# Processor.net
KiCad netlist of a schematic drawn in Altium Designer
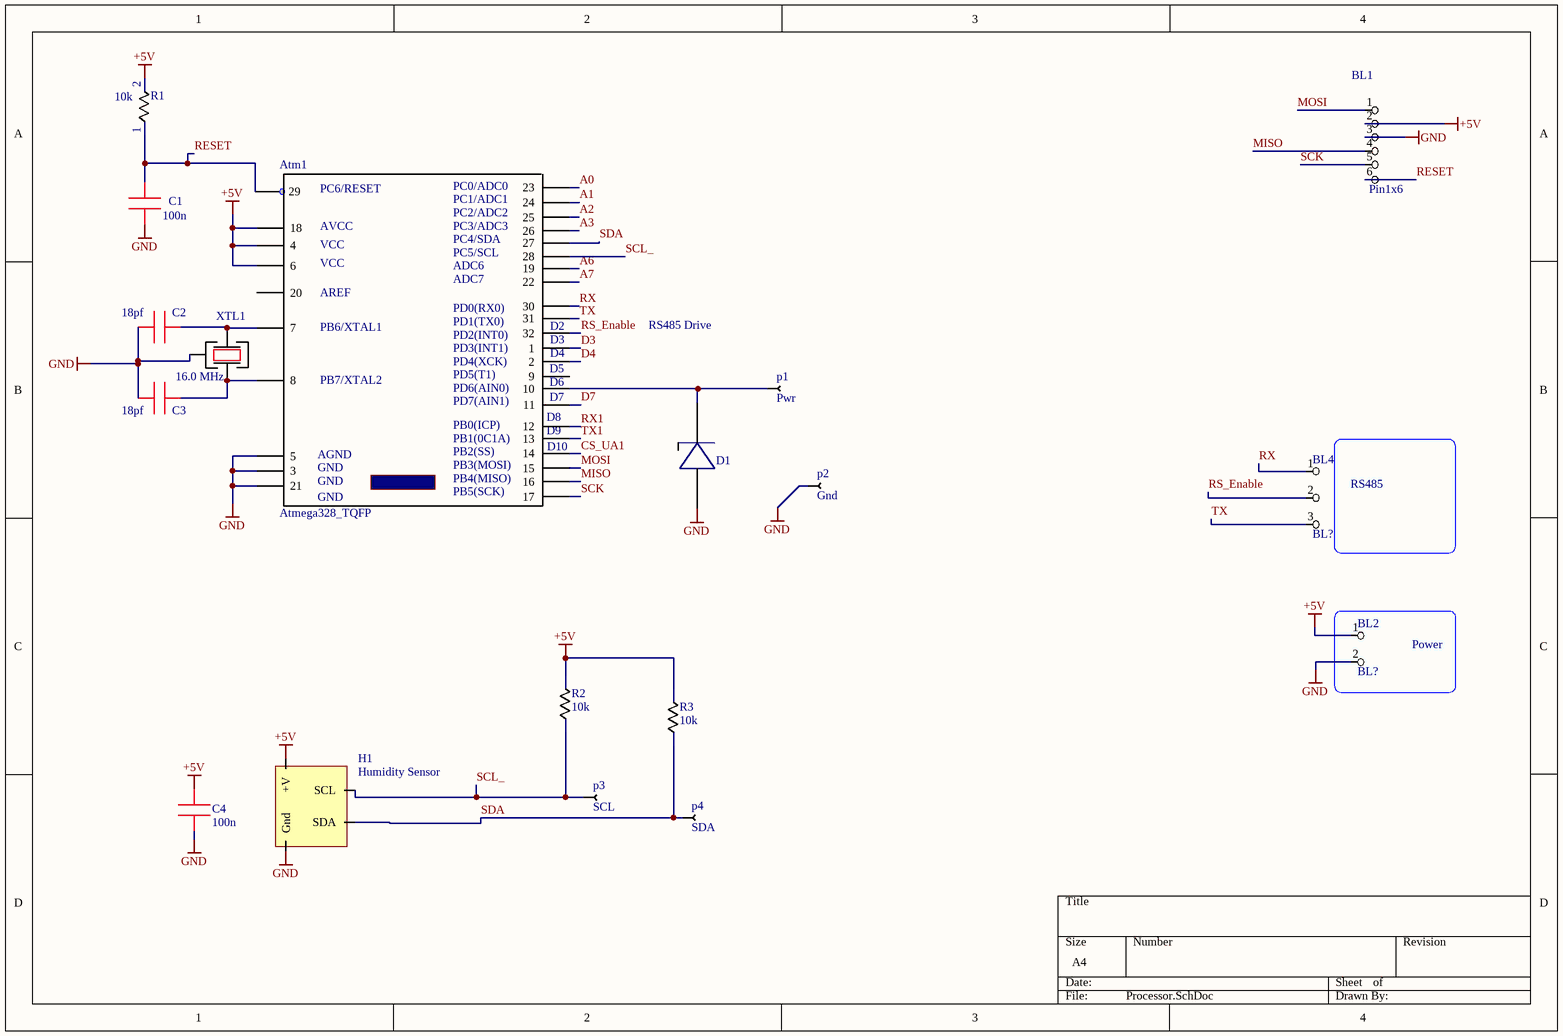
[diagram p0: Processor.SchDoc]

(export (version "E")
  (design (tool "Eeschema 10.0.6"))
  (components
    (comp (ref "Atm1")
      (value "Atmega328_TQFP")
      (footprint "TQFP")
      (libsource (lib "kontr") (part "Atmega328_TQFP"))
    )
    (comp (ref "BL1")
      (value "Pin1x6")
      (footprint "Pin_6 1,27")
      (description "PLL-6")
      (libsource (lib "kontr") (part "Pin1x6"))
    )
    (comp (ref "BL2") (value "BL?") (footprint "2.54 2pin") (libsource (lib "kontr") (part "2.54 2pin")))
    (comp (ref "BL4") (value "BL?") (footprint "2.54 3pin") (libsource (lib "kontr") (part "2.54 3pin")))
    (comp (ref "C1")
      (value "100n")
      (footprint "0402")
      (description "C1005X7R1H104K050BB")
      (libsource (lib "kontr") (part "Capasitor 0805"))
    )
    (comp (ref "C2")
      (value "18pf")
      (footprint "0402")
      (description "CC0402JRNPO9BN180")
      (libsource (lib "kontr") (part "Capasitor 0805"))
    )
    (comp (ref "C3")
      (value "18pf")
      (footprint "0402")
      (description "CC0402JRNPO9BN180")
      (libsource (lib "kontr") (part "Capasitor 0805"))
    )
    (comp (ref "C4")
      (value "100n")
      (footprint "0402")
      (description "C1005X7R1H104K050BB")
      (libsource (lib "kontr") (part "0805 Cap"))
    )
    (comp (ref "D1")
      (value "zener")
      (footprint "Sot23-3")
      (description "BZX84C5V6LT1G")
      (libsource (lib "kontr") (part "BZX84"))
    )
    (comp (ref "H1")
      (value "Humidity Sensor")
      (footprint "TO39_Moist")
      (libsource (lib "kontr") (part "HYT 939"))
    )
    (comp (ref "p1")
      (value "Pwr")
      (footprint "Wire Pin 0.5")
      (description "pin")
      (libsource (lib "kontr") (part "PIN_Wire"))
    )
    (comp (ref "p2")
      (value "Gnd")
      (footprint "Wire Pin 0.5")
      (description "pin")
      (libsource (lib "kontr") (part "PIN_Wire"))
    )
    (comp (ref "p3")
      (value "SCL")
      (footprint "Wire Pin 0.5")
      (description "pin")
      (libsource (lib "kontr") (part "PIN_Wire"))
    )
    (comp (ref "p4")
      (value "SDA")
      (footprint "Wire Pin 0.5")
      (description "pin")
      (libsource (lib "kontr") (part "PIN_Wire"))
    )
    (comp (ref "R1")
      (value "10k")
      (footprint "0402")
      (description "RC0402FR-0710KL")
      (libsource (lib "") (part "Resistor 0805_1"))
    )
    (comp (ref "R2")
      (value "10k")
      (footprint "0402")
      (description "RC0402FR-0710KL")
      (libsource (lib "kontr") (part "Resistor 0805"))
    )
    (comp (ref "R3")
      (value "10k")
      (footprint "0402")
      (description "RC0402FR-0710KL")
      (libsource (lib "kontr") (part "Resistor 0805"))
    )
    (comp (ref "XTL1")
      (value "16.0 MHz")
      (footprint "KX-7 XTAL")
      (description "KX-7T 16.0 MHz 50/100/100")
      (libsource (lib "kontr") (part "KX-7"))
    )
  )
  (nets
    (net (code "1") (name "+5V") (class "Default")
      (node (ref "Atm1") (pin "18") (pinfunction "18_18") (pintype "passive"))
      (node (ref "Atm1") (pin "4") (pinfunction "4_4") (pintype "passive"))
      (node (ref "Atm1") (pin "6") (pinfunction "6_6") (pintype "passive"))
      (node (ref "BL1") (pin "2") (pinfunction "2_2") (pintype "passive"))
      (node (ref "BL2") (pin "1") (pinfunction "1_1") (pintype "passive"))
      (node (ref "C4") (pin "2") (pinfunction "2_2") (pintype "passive"))
      (node (ref "H1") (pin "2") (pinfunction "+V_2") (pintype "passive"))
      (node (ref "R1") (pin "2") (pintype "passive"))
      (node (ref "R2") (pin "2") (pintype "passive"))
      (node (ref "R3") (pin "2") (pintype "passive"))
    )
    (net (code "2") (name "/A0") (class "Default")
      (node (ref "Atm1") (pin "23") (pinfunction "23_23") (pintype "passive"))
    )
    (net (code "3") (name "/A1") (class "Default")
      (node (ref "Atm1") (pin "24") (pinfunction "24_24") (pintype "passive"))
    )
    (net (code "4") (name "/A2") (class "Default")
      (node (ref "Atm1") (pin "25") (pinfunction "25_25") (pintype "passive"))
    )
    (net (code "5") (name "/A3") (class "Default")
      (node (ref "Atm1") (pin "26") (pinfunction "26_26") (pintype "passive"))
    )
    (net (code "6") (name "/A6") (class "Default")
      (node (ref "Atm1") (pin "19") (pinfunction "19_19") (pintype "passive"))
    )
    (net (code "7") (name "/A7") (class "Default")
      (node (ref "Atm1") (pin "22") (pinfunction "22_22") (pintype "passive"))
    )
    (net (code "8") (name "/CS_UA1") (class "Default")
      (node (ref "Atm1") (pin "14") (pinfunction "14_14") (pintype "passive"))
    )
    (net (code "9") (name "/D3") (class "Default")
      (node (ref "Atm1") (pin "1") (pinfunction "1_1") (pintype "passive"))
    )
    (net (code "10") (name "/D4") (class "Default")
      (node (ref "Atm1") (pin "2") (pinfunction "2_2") (pintype "passive"))
    )
    (net (code "11") (name "/D7") (class "Default")
      (node (ref "Atm1") (pin "11") (pinfunction "11_11") (pintype "passive"))
    )
    (net (code "12") (name "/MISO") (class "Default")
      (node (ref "Atm1") (pin "16") (pinfunction "16_16") (pintype "passive"))
      (node (ref "BL1") (pin "4") (pinfunction "4_4") (pintype "passive"))
    )
    (net (code "13") (name "/MOSI") (class "Default")
      (node (ref "Atm1") (pin "15") (pinfunction "15_15") (pintype "passive"))
      (node (ref "BL1") (pin "1") (pinfunction "1_1") (pintype "passive"))
    )
    (net (code "14") (name "/RESET") (class "Default")
      (node (ref "Atm1") (pin "29") (pinfunction "29_29") (pintype "passive"))
      (node (ref "BL1") (pin "6") (pinfunction "6_6") (pintype "passive"))
      (node (ref "C1") (pin "2") (pinfunction "2_2") (pintype "passive"))
      (node (ref "R1") (pin "1") (pintype "passive"))
    )
    (net (code "15") (name "/RS_Enable") (class "Default")
      (node (ref "Atm1") (pin "32") (pinfunction "32_32") (pintype "passive"))
      (node (ref "BL4") (pin "2") (pinfunction "2_2") (pintype "passive"))
    )
    (net (code "16") (name "/RX") (class "Default")
      (node (ref "Atm1") (pin "30") (pinfunction "30_30") (pintype "passive"))
      (node (ref "BL4") (pin "1") (pinfunction "1_1") (pintype "passive"))
    )
    (net (code "17") (name "/RX1") (class "Default")
      (node (ref "Atm1") (pin "12") (pinfunction "12_12") (pintype "passive"))
    )
    (net (code "18") (name "/SCK") (class "Default")
      (node (ref "Atm1") (pin "17") (pinfunction "17_17") (pintype "passive"))
      (node (ref "BL1") (pin "5") (pinfunction "5_5") (pintype "passive"))
    )
    (net (code "19") (name "/SCL_") (class "Default")
      (node (ref "Atm1") (pin "28") (pinfunction "28_28") (pintype "passive"))
      (node (ref "H1") (pin "1") (pinfunction "SCL_1") (pintype "passive"))
      (node (ref "R2") (pin "1") (pintype "passive"))
      (node (ref "p3") (pin "1") (pinfunction "1_1") (pintype "passive"))
    )
    (net (code "20") (name "/SDA") (class "Default")
      (node (ref "Atm1") (pin "27") (pinfunction "27_27") (pintype "passive"))
      (node (ref "H1") (pin "4") (pinfunction "SDA_4") (pintype "passive"))
      (node (ref "R3") (pin "1") (pintype "passive"))
      (node (ref "p4") (pin "1") (pinfunction "1_1") (pintype "passive"))
    )
    (net (code "21") (name "/TX") (class "Default")
      (node (ref "Atm1") (pin "31") (pinfunction "31_31") (pintype "passive"))
      (node (ref "BL4") (pin "3") (pinfunction "3_3") (pintype "passive"))
    )
    (net (code "22") (name "/TX1") (class "Default")
      (node (ref "Atm1") (pin "13") (pinfunction "13_13") (pintype "passive"))
    )
    (net (code "23") (name "GND") (class "Default")
      (node (ref "Atm1") (pin "21") (pinfunction "21_21") (pintype "passive"))
      (node (ref "Atm1") (pin "3") (pinfunction "3_3") (pintype "passive"))
      (node (ref "Atm1") (pin "5") (pinfunction "5_5") (pintype "passive"))
      (node (ref "BL1") (pin "3") (pinfunction "3_3") (pintype "passive"))
      (node (ref "BL2") (pin "2") (pinfunction "2_2") (pintype "passive"))
      (node (ref "C1") (pin "1") (pinfunction "1_1") (pintype "passive"))
      (node (ref "C2") (pin "1") (pinfunction "1_1") (pintype "passive"))
      (node (ref "C3") (pin "1") (pinfunction "1_1") (pintype "passive"))
      (node (ref "C4") (pin "1") (pinfunction "1_1") (pintype "passive"))
      (node (ref "D1") (pin "1") (pinfunction "1_1") (pintype "passive"))
      (node (ref "H1") (pin "3") (pinfunction "Gnd_3") (pintype "passive"))
      (node (ref "XTL1") (pin "2") (pinfunction "2_2") (pintype "passive"))
      (node (ref "p2") (pin "1") (pinfunction "1_1") (pintype "passive"))
    )
    (net (code "24") (name "Net-(Atm1-Pad7)") (class "Default")
      (node (ref "Atm1") (pin "7") (pinfunction "7_7") (pintype "passive"))
      (node (ref "C2") (pin "2") (pinfunction "2_2") (pintype "passive"))
      (node (ref "XTL1") (pin "1") (pinfunction "5_1") (pintype "passive"))
    )
    (net (code "25") (name "Net-(Atm1-Pad8)") (class "Default")
      (node (ref "Atm1") (pin "8") (pinfunction "8_8") (pintype "passive"))
      (node (ref "C3") (pin "2") (pinfunction "2_2") (pintype "passive"))
      (node (ref "XTL1") (pin "3") (pinfunction "5_3") (pintype "passive"))
    )
    (net (code "26") (name "Net-(Atm1-Pad10)") (class "Default")
      (node (ref "Atm1") (pin "10") (pinfunction "10_10") (pintype "passive"))
      (node (ref "D1") (pin "3") (pinfunction "3_3") (pintype "passive"))
      (node (ref "p1") (pin "1") (pinfunction "1_1") (pintype "passive"))
    )
    (net (code "27") (name "unconnected-(Atm1-Pad9)") (class "Default")
      (node (ref "Atm1") (pin "9") (pinfunction "9_9") (pintype "passive"))
    )
    (net (code "28") (name "unconnected-(Atm1-Pad20)") (class "Default")
      (node (ref "Atm1") (pin "20") (pinfunction "20_20") (pintype "passive"))
    )
  )
)
